# CW308T_SAM4L_UFO.net
KiCad netlist of a schematic drawn in Altium Designer
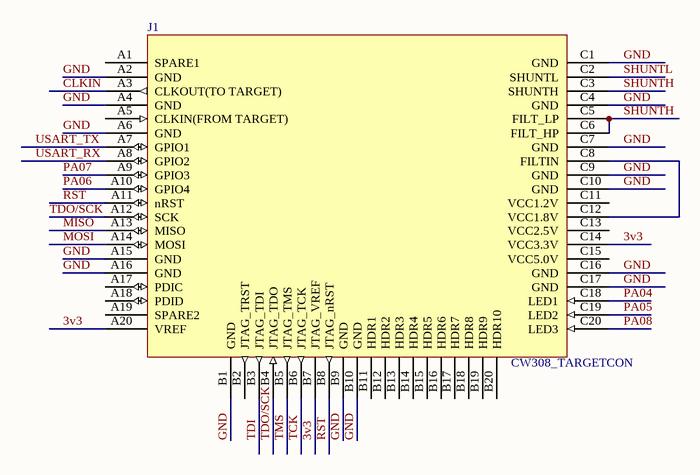
[diagram p0: CW308T_SAM4L_UFO.SchDoc]

(export (version "E")
  (design (tool "Eeschema 10.0.6"))
  (components
    (comp (ref "J1")
      (value "CW308_TARGETCON")
      (footprint "CW308_TBOARD_CONN")
      (description "CW308 \"Standard\" Target Board Connector")
      (fields (field (name "PART NUMBER") "CW308_TBOARD"))
      (libsource (lib "NewAE_AltiumLib") (part "CW308_TBOARD"))
    )
  )
  (nets
    (net (code "1") (name "/3v3") (class "Default")
      (node (ref "J1") (pin "A20") (pinfunction "VREF_A20") (pintype "tri_state"))
      (node (ref "J1") (pin "B7") (pinfunction "JTAG_VREF_B7") (pintype "tri_state"))
      (node (ref "J1") (pin "C14") (pinfunction "VCC3.3V_C14") (pintype "power_in"))
    )
    (net (code "2") (name "/CLKIN") (class "Default")
      (node (ref "J1") (pin "A3") (pinfunction "CLKOUT(TO_TARGET)_A3") (pintype "output"))
    )
    (net (code "3") (name "/GND") (class "Default")
      (node (ref "J1") (pin "A15") (pinfunction "GND_A15") (pintype "passive"))
      (node (ref "J1") (pin "A16") (pinfunction "GND_A16") (pintype "passive"))
      (node (ref "J1") (pin "A2") (pinfunction "GND_A2") (pintype "passive"))
      (node (ref "J1") (pin "A4") (pinfunction "GND_A4") (pintype "passive"))
      (node (ref "J1") (pin "A6") (pinfunction "GND_A6") (pintype "power_in"))
      (node (ref "J1") (pin "B1") (pinfunction "GND_B1") (pintype "passive"))
      (node (ref "J1") (pin "B10") (pinfunction "GND_B10") (pintype "passive"))
      (node (ref "J1") (pin "B9") (pinfunction "GND_B9") (pintype "passive"))
      (node (ref "J1") (pin "C1") (pinfunction "GND_C1") (pintype "power_in"))
      (node (ref "J1") (pin "C10") (pinfunction "GND_C10") (pintype "power_in"))
      (node (ref "J1") (pin "C16") (pinfunction "GND_C16") (pintype "power_in"))
      (node (ref "J1") (pin "C17") (pinfunction "GND_C17") (pintype "power_in"))
      (node (ref "J1") (pin "C4") (pinfunction "GND_C4") (pintype "power_in"))
      (node (ref "J1") (pin "C7") (pinfunction "GND_C7") (pintype "power_in"))
      (node (ref "J1") (pin "C9") (pinfunction "GND_C9") (pintype "power_in"))
    )
    (net (code "4") (name "/MISO") (class "Default")
      (node (ref "J1") (pin "A13") (pinfunction "MISO_A13") (pintype "bidirectional"))
    )
    (net (code "5") (name "/MOSI") (class "Default")
      (node (ref "J1") (pin "A14") (pinfunction "MOSI_A14") (pintype "bidirectional"))
    )
    (net (code "6") (name "/PA04") (class "Default")
      (node (ref "J1") (pin "C18") (pinfunction "LED1_C18") (pintype "input"))
    )
    (net (code "7") (name "/PA05") (class "Default")
      (node (ref "J1") (pin "C19") (pinfunction "LED2_C19") (pintype "input"))
    )
    (net (code "8") (name "/PA06") (class "Default")
      (node (ref "J1") (pin "A10") (pinfunction "GPIO4_A10") (pintype "bidirectional"))
    )
    (net (code "9") (name "/PA07") (class "Default")
      (node (ref "J1") (pin "A9") (pinfunction "GPIO3_A9") (pintype "bidirectional"))
    )
    (net (code "10") (name "/PA08") (class "Default")
      (node (ref "J1") (pin "C20") (pinfunction "LED3_C20") (pintype "input"))
    )
    (net (code "11") (name "/RST") (class "Default")
      (node (ref "J1") (pin "A11") (pinfunction "nRST_A11") (pintype "bidirectional"))
      (node (ref "J1") (pin "B8") (pinfunction "JTAG_nRST_B8") (pintype "output"))
    )
    (net (code "12") (name "/SHUNTH") (class "Default")
      (node (ref "J1") (pin "C3") (pinfunction "SHUNTH_C3") (pintype "passive"))
      (node (ref "J1") (pin "C5") (pinfunction "FILT_LP_C5") (pintype "passive"))
      (node (ref "J1") (pin "C6") (pinfunction "FILT_HP_C6") (pintype "passive"))
    )
    (net (code "13") (name "/SHUNTL") (class "Default")
      (node (ref "J1") (pin "C2") (pinfunction "SHUNTL_C2") (pintype "passive"))
    )
    (net (code "14") (name "/TCK") (class "Default")
      (node (ref "J1") (pin "B6") (pinfunction "JTAG_TCK_B6") (pintype "output"))
    )
    (net (code "15") (name "/TDI") (class "Default")
      (node (ref "J1") (pin "B3") (pinfunction "JTAG_TDI_B3") (pintype "output"))
    )
    (net (code "16") (name "/TDO{slash}SCK") (class "Default")
      (node (ref "J1") (pin "A12") (pinfunction "SCK_A12") (pintype "bidirectional"))
      (node (ref "J1") (pin "B4") (pinfunction "JTAG_TDO_B4") (pintype "input"))
    )
    (net (code "17") (name "/TMS") (class "Default")
      (node (ref "J1") (pin "B5") (pinfunction "JTAG_TMS_B5") (pintype "output"))
    )
    (net (code "18") (name "/USART_RX") (class "Default")
      (node (ref "J1") (pin "A8") (pinfunction "GPIO2_A8") (pintype "bidirectional"))
    )
    (net (code "19") (name "/USART_TX") (class "Default")
      (node (ref "J1") (pin "A7") (pinfunction "GPIO1_A7") (pintype "bidirectional"))
    )
    (net (code "20") (name "Net-(J1-FILTIN)") (class "Default")
      (node (ref "J1") (pin "C12") (pinfunction "VCC1.8V_C12") (pintype "power_in"))
      (node (ref "J1") (pin "C8") (pinfunction "FILTIN_C8") (pintype "passive"))
    )
    (net (code "21") (name "unconnected-(J1-CLKIN(FROM_TARGET)-PadA5)") (class "Default")
      (node (ref "J1") (pin "A5") (pinfunction "CLKIN(FROM_TARGET)_A5") (pintype "input"))
    )
    (net (code "22") (name "unconnected-(J1-HDR1-PadB11)") (class "Default")
      (node (ref "J1") (pin "B11") (pinfunction "HDR1_B11") (pintype "passive"))
    )
    (net (code "23") (name "unconnected-(J1-HDR2-PadB12)") (class "Default")
      (node (ref "J1") (pin "B12") (pinfunction "HDR2_B12") (pintype "passive"))
    )
    (net (code "24") (name "unconnected-(J1-HDR3-PadB13)") (class "Default")
      (node (ref "J1") (pin "B13") (pinfunction "HDR3_B13") (pintype "passive"))
    )
    (net (code "25") (name "unconnected-(J1-HDR4-PadB14)") (class "Default")
      (node (ref "J1") (pin "B14") (pinfunction "HDR4_B14") (pintype "passive"))
    )
    (net (code "26") (name "unconnected-(J1-HDR5-PadB15)") (class "Default")
      (node (ref "J1") (pin "B15") (pinfunction "HDR5_B15") (pintype "passive"))
    )
    (net (code "27") (name "unconnected-(J1-HDR6-PadB16)") (class "Default")
      (node (ref "J1") (pin "B16") (pinfunction "HDR6_B16") (pintype "passive"))
    )
    (net (code "28") (name "unconnected-(J1-HDR7-PadB17)") (class "Default")
      (node (ref "J1") (pin "B17") (pinfunction "HDR7_B17") (pintype "passive"))
    )
    (net (code "29") (name "unconnected-(J1-HDR8-PadB18)") (class "Default")
      (node (ref "J1") (pin "B18") (pinfunction "HDR8_B18") (pintype "passive"))
    )
    (net (code "30") (name "unconnected-(J1-HDR9-PadB19)") (class "Default")
      (node (ref "J1") (pin "B19") (pinfunction "HDR9_B19") (pintype "passive"))
    )
    (net (code "31") (name "unconnected-(J1-HDR10-PadB20)") (class "Default")
      (node (ref "J1") (pin "B20") (pinfunction "HDR10_B20") (pintype "passive"))
    )
    (net (code "32") (name "unconnected-(J1-JTAG_TRST-PadB2)") (class "Default")
      (node (ref "J1") (pin "B2") (pinfunction "JTAG_TRST_B2") (pintype "output"))
    )
    (net (code "33") (name "unconnected-(J1-PDIC-PadA17)") (class "Default")
      (node (ref "J1") (pin "A17") (pinfunction "PDIC_A17") (pintype "bidirectional"))
    )
    (net (code "34") (name "unconnected-(J1-PDID-PadA18)") (class "Default")
      (node (ref "J1") (pin "A18") (pinfunction "PDID_A18") (pintype "bidirectional"))
    )
    (net (code "35") (name "unconnected-(J1-SPARE1-PadA1)") (class "Default")
      (node (ref "J1") (pin "A1") (pinfunction "SPARE1_A1") (pintype "passive"))
    )
    (net (code "36") (name "unconnected-(J1-SPARE2-PadA19)") (class "Default")
      (node (ref "J1") (pin "A19") (pinfunction "SPARE2_A19") (pintype "passive"))
    )
    (net (code "37") (name "unconnected-(J1-VCC1.2V-PadC11)") (class "Default")
      (node (ref "J1") (pin "C11") (pinfunction "VCC1.2V_C11") (pintype "power_in"))
    )
    (net (code "38") (name "unconnected-(J1-VCC2.5V-PadC13)") (class "Default")
      (node (ref "J1") (pin "C13") (pinfunction "VCC2.5V_C13") (pintype "power_in"))
    )
    (net (code "39") (name "unconnected-(J1-VCC5.0V-PadC15)") (class "Default")
      (node (ref "J1") (pin "C15") (pinfunction "VCC5.0V_C15") (pintype "power_in"))
    )
  )
)
